# greenbox.net
KiCad netlist of a schematic drawn in EAGLE
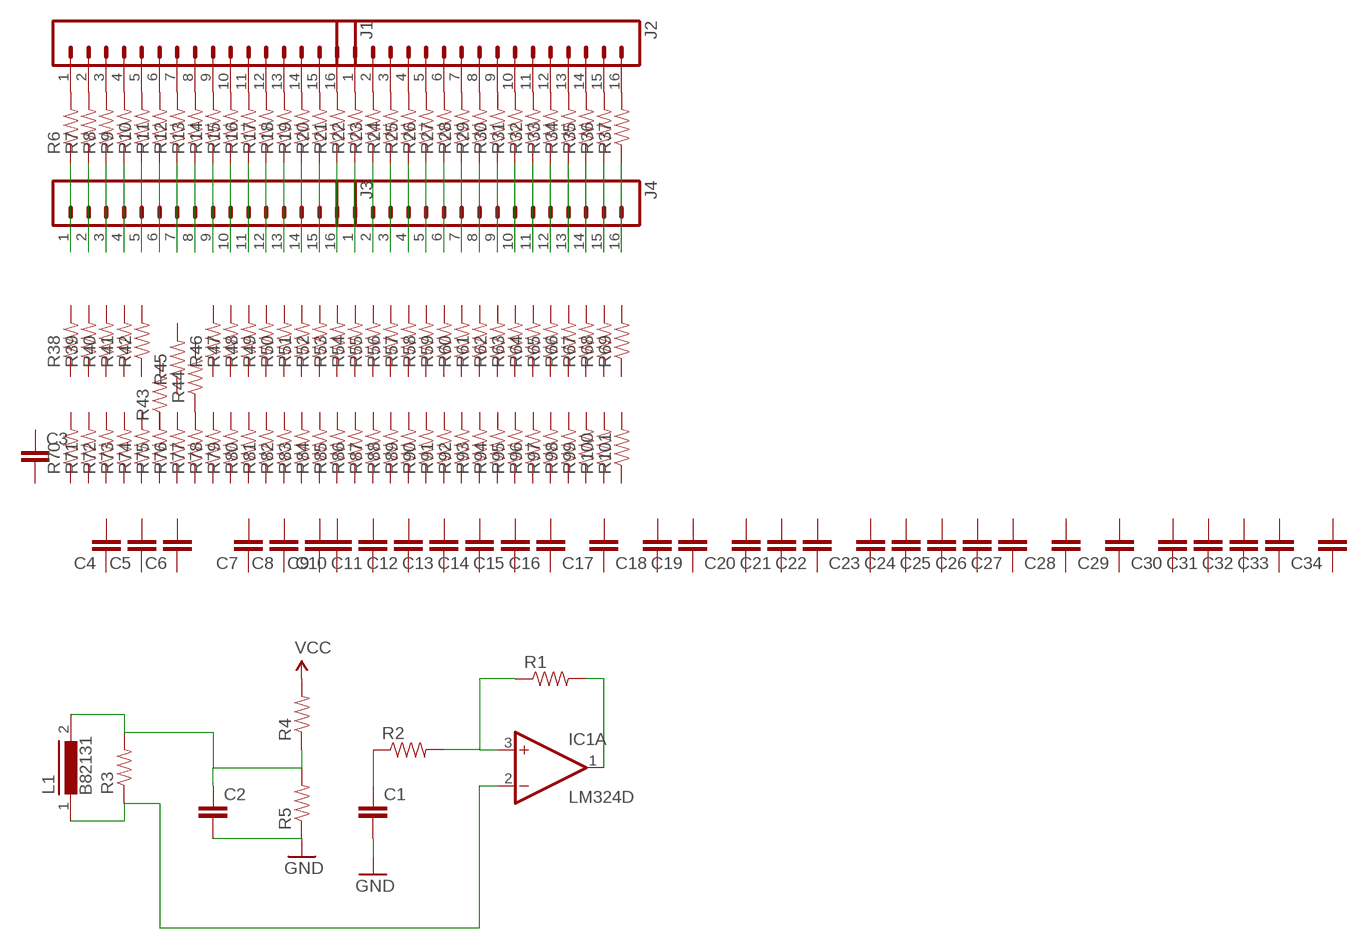
[diagram p0: schematic, sheet 1]

(export (version "E")
  (design (tool "Eeschema 10.0.6"))
  (components
    (comp (ref "C1")
      (value "CAP0603-CAP")
      (footprint "eagle-import:0603-CAP")
      (libsource (lib "eagle-import") (part "SparkFun-Passives_CAP0603-CAP"))
    )
    (comp (ref "C2")
      (value "CAP0603-CAP")
      (footprint "eagle-import:0603-CAP")
      (libsource (lib "eagle-import") (part "SparkFun-Passives_CAP0603-CAP"))
    )
    (comp (ref "C3")
      (value "CAP0603-CAP")
      (footprint "eagle-import:0603-CAP")
      (libsource (lib "eagle-import") (part "CAP0603-CAP"))
    )
    (comp (ref "C4")
      (value "CAP0603-CAP")
      (footprint "eagle-import:0603-CAP")
      (libsource (lib "eagle-import") (part "CAP0603-CAP"))
    )
    (comp (ref "C5")
      (value "CAP0603-CAP")
      (footprint "eagle-import:0603-CAP")
      (libsource (lib "eagle-import") (part "CAP0603-CAP"))
    )
    (comp (ref "C6")
      (value "CAP0603-CAP")
      (footprint "eagle-import:0603-CAP")
      (libsource (lib "eagle-import") (part "CAP0603-CAP"))
    )
    (comp (ref "C7")
      (value "CAP0603-CAP")
      (footprint "eagle-import:0603-CAP")
      (libsource (lib "eagle-import") (part "CAP0603-CAP"))
    )
    (comp (ref "C8")
      (value "CAP0603-CAP")
      (footprint "eagle-import:0603-CAP")
      (libsource (lib "eagle-import") (part "CAP0603-CAP"))
    )
    (comp (ref "C9")
      (value "CAP0603-CAP")
      (footprint "eagle-import:0603-CAP")
      (libsource (lib "eagle-import") (part "CAP0603-CAP"))
    )
    (comp (ref "C10")
      (value "CAP0603-CAP")
      (footprint "eagle-import:0603-CAP")
      (libsource (lib "eagle-import") (part "CAP0603-CAP"))
    )
    (comp (ref "C11")
      (value "CAP0603-CAP")
      (footprint "eagle-import:0603-CAP")
      (libsource (lib "eagle-import") (part "CAP0603-CAP"))
    )
    (comp (ref "C12")
      (value "CAP0603-CAP")
      (footprint "eagle-import:0603-CAP")
      (libsource (lib "eagle-import") (part "CAP0603-CAP"))
    )
    (comp (ref "C13")
      (value "CAP0603-CAP")
      (footprint "eagle-import:0603-CAP")
      (libsource (lib "eagle-import") (part "CAP0603-CAP"))
    )
    (comp (ref "C14")
      (value "CAP0603-CAP")
      (footprint "eagle-import:0603-CAP")
      (libsource (lib "eagle-import") (part "CAP0603-CAP"))
    )
    (comp (ref "C15")
      (value "CAP0603-CAP")
      (footprint "eagle-import:0603-CAP")
      (libsource (lib "eagle-import") (part "CAP0603-CAP"))
    )
    (comp (ref "C16")
      (value "CAP0603-CAP")
      (footprint "eagle-import:0603-CAP")
      (libsource (lib "eagle-import") (part "CAP0603-CAP"))
    )
    (comp (ref "C17")
      (value "CAP0603-CAP")
      (footprint "eagle-import:0603-CAP")
      (libsource (lib "eagle-import") (part "CAP0603-CAP"))
    )
    (comp (ref "C18")
      (value "CAP0603-CAP")
      (footprint "eagle-import:0603-CAP")
      (libsource (lib "eagle-import") (part "CAP0603-CAP"))
    )
    (comp (ref "C19")
      (value "CAP0603-CAP")
      (footprint "eagle-import:0603-CAP")
      (libsource (lib "eagle-import") (part "CAP0603-CAP"))
    )
    (comp (ref "C20")
      (value "CAP0603-CAP")
      (footprint "eagle-import:0603-CAP")
      (libsource (lib "eagle-import") (part "CAP0603-CAP"))
    )
    (comp (ref "C21")
      (value "CAP0603-CAP")
      (footprint "eagle-import:0603-CAP")
      (libsource (lib "eagle-import") (part "CAP0603-CAP"))
    )
    (comp (ref "C22")
      (value "CAP0603-CAP")
      (footprint "eagle-import:0603-CAP")
      (libsource (lib "eagle-import") (part "CAP0603-CAP"))
    )
    (comp (ref "C23")
      (value "CAP0603-CAP")
      (footprint "eagle-import:0603-CAP")
      (libsource (lib "eagle-import") (part "CAP0603-CAP"))
    )
    (comp (ref "C24")
      (value "CAP0603-CAP")
      (footprint "eagle-import:0603-CAP")
      (libsource (lib "eagle-import") (part "CAP0603-CAP"))
    )
    (comp (ref "C25")
      (value "CAP0603-CAP")
      (footprint "eagle-import:0603-CAP")
      (libsource (lib "eagle-import") (part "CAP0603-CAP"))
    )
    (comp (ref "C26")
      (value "CAP0603-CAP")
      (footprint "eagle-import:0603-CAP")
      (libsource (lib "eagle-import") (part "CAP0603-CAP"))
    )
    (comp (ref "C27")
      (value "CAP0603-CAP")
      (footprint "eagle-import:0603-CAP")
      (libsource (lib "eagle-import") (part "CAP0603-CAP"))
    )
    (comp (ref "C28")
      (value "CAP0603-CAP")
      (footprint "eagle-import:0603-CAP")
      (libsource (lib "eagle-import") (part "CAP0603-CAP"))
    )
    (comp (ref "C29")
      (value "CAP0603-CAP")
      (footprint "eagle-import:0603-CAP")
      (libsource (lib "eagle-import") (part "CAP0603-CAP"))
    )
    (comp (ref "C30")
      (value "CAP0603-CAP")
      (footprint "eagle-import:0603-CAP")
      (libsource (lib "eagle-import") (part "CAP0603-CAP"))
    )
    (comp (ref "C31")
      (value "CAP0603-CAP")
      (footprint "eagle-import:0603-CAP")
      (libsource (lib "eagle-import") (part "CAP0603-CAP"))
    )
    (comp (ref "C32")
      (value "CAP0603-CAP")
      (footprint "eagle-import:0603-CAP")
      (libsource (lib "eagle-import") (part "CAP0603-CAP"))
    )
    (comp (ref "C33")
      (value "CAP0603-CAP")
      (footprint "eagle-import:0603-CAP")
      (libsource (lib "eagle-import") (part "CAP0603-CAP"))
    )
    (comp (ref "C34")
      (value "CAP0603-CAP")
      (footprint "eagle-import:0603-CAP")
      (libsource (lib "eagle-import") (part "CAP0603-CAP"))
    )
    (comp (ref "IC1")
      (value "LM324D")
      (footprint "eagle-import:SO14")
      (libsource (lib "eagle-import") (part "LM324D"))
    )
    (comp (ref "J1")
      (value "M16LOCK")
      (footprint "eagle-import:1X16_LOCK")
      (libsource (lib "eagle-import") (part "M16LOCK"))
    )
    (comp (ref "J2")
      (value "M16LOCK")
      (footprint "eagle-import:1X16_LOCK")
      (libsource (lib "eagle-import") (part "M16LOCK"))
    )
    (comp (ref "J3")
      (value "M16LOCK")
      (footprint "eagle-import:1X16_LOCK")
      (libsource (lib "eagle-import") (part "M16LOCK"))
    )
    (comp (ref "J4")
      (value "M16LOCK")
      (footprint "eagle-import:1X16_LOCK")
      (libsource (lib "eagle-import") (part "M16LOCK"))
    )
    (comp (ref "L1")
      (value "B82131")
      (footprint "eagle-import:SUKW1-17")
      (libsource (lib "eagle-import") (part "B82131"))
    )
    (comp (ref "R1")
      (value "RESISTOR0603")
      (footprint "eagle-import:0603-RES")
      (libsource (lib "eagle-import") (part "RESISTOR0603"))
    )
    (comp (ref "R2")
      (value "RESISTOR0603")
      (footprint "eagle-import:0603-RES")
      (libsource (lib "eagle-import") (part "RESISTOR0603"))
    )
    (comp (ref "R3")
      (value "RESISTOR0603-RES")
      (footprint "eagle-import:0603-RES")
      (libsource (lib "eagle-import") (part "RESISTOR0603-RES"))
    )
    (comp (ref "R4")
      (value "RESISTOR0603-RES")
      (footprint "eagle-import:0603-RES")
      (libsource (lib "eagle-import") (part "RESISTOR0603-RES"))
    )
    (comp (ref "R5")
      (value "RESISTOR0603-RES")
      (footprint "eagle-import:0603-RES")
      (libsource (lib "eagle-import") (part "RESISTOR0603-RES"))
    )
    (comp (ref "R6")
      (value "RESISTOR0603-RES")
      (footprint "eagle-import:0603-RES")
      (libsource (lib "eagle-import") (part "RESISTOR0603-RES"))
    )
    (comp (ref "R7")
      (value "RESISTOR0603-RES")
      (footprint "eagle-import:0603-RES")
      (libsource (lib "eagle-import") (part "RESISTOR0603-RES"))
    )
    (comp (ref "R8")
      (value "RESISTOR0603-RES")
      (footprint "eagle-import:0603-RES")
      (libsource (lib "eagle-import") (part "RESISTOR0603-RES"))
    )
    (comp (ref "R9")
      (value "RESISTOR0603-RES")
      (footprint "eagle-import:0603-RES")
      (libsource (lib "eagle-import") (part "RESISTOR0603-RES"))
    )
    (comp (ref "R10")
      (value "RESISTOR0603-RES")
      (footprint "eagle-import:0603-RES")
      (libsource (lib "eagle-import") (part "RESISTOR0603-RES"))
    )
    (comp (ref "R11")
      (value "RESISTOR0603-RES")
      (footprint "eagle-import:0603-RES")
      (libsource (lib "eagle-import") (part "RESISTOR0603-RES"))
    )
    (comp (ref "R12")
      (value "RESISTOR0603-RES")
      (footprint "eagle-import:0603-RES")
      (libsource (lib "eagle-import") (part "RESISTOR0603-RES"))
    )
    (comp (ref "R13")
      (value "RESISTOR0603-RES")
      (footprint "eagle-import:0603-RES")
      (libsource (lib "eagle-import") (part "RESISTOR0603-RES"))
    )
    (comp (ref "R14")
      (value "RESISTOR0603-RES")
      (footprint "eagle-import:0603-RES")
      (libsource (lib "eagle-import") (part "RESISTOR0603-RES"))
    )
    (comp (ref "R15")
      (value "RESISTOR0603-RES")
      (footprint "eagle-import:0603-RES")
      (libsource (lib "eagle-import") (part "RESISTOR0603-RES"))
    )
    (comp (ref "R16")
      (value "RESISTOR0603-RES")
      (footprint "eagle-import:0603-RES")
      (libsource (lib "eagle-import") (part "RESISTOR0603-RES"))
    )
    (comp (ref "R17")
      (value "RESISTOR0603-RES")
      (footprint "eagle-import:0603-RES")
      (libsource (lib "eagle-import") (part "RESISTOR0603-RES"))
    )
    (comp (ref "R18")
      (value "RESISTOR0603-RES")
      (footprint "eagle-import:0603-RES")
      (libsource (lib "eagle-import") (part "RESISTOR0603-RES"))
    )
    (comp (ref "R19")
      (value "RESISTOR0603-RES")
      (footprint "eagle-import:0603-RES")
      (libsource (lib "eagle-import") (part "RESISTOR0603-RES"))
    )
    (comp (ref "R20")
      (value "RESISTOR0603-RES")
      (footprint "eagle-import:0603-RES")
      (libsource (lib "eagle-import") (part "RESISTOR0603-RES"))
    )
    (comp (ref "R21")
      (value "RESISTOR0603-RES")
      (footprint "eagle-import:0603-RES")
      (libsource (lib "eagle-import") (part "RESISTOR0603-RES"))
    )
    (comp (ref "R22")
      (value "RESISTOR0603-RES")
      (footprint "eagle-import:0603-RES")
      (libsource (lib "eagle-import") (part "RESISTOR0603-RES"))
    )
    (comp (ref "R23")
      (value "RESISTOR0603-RES")
      (footprint "eagle-import:0603-RES")
      (libsource (lib "eagle-import") (part "RESISTOR0603-RES"))
    )
    (comp (ref "R24")
      (value "RESISTOR0603-RES")
      (footprint "eagle-import:0603-RES")
      (libsource (lib "eagle-import") (part "RESISTOR0603-RES"))
    )
    (comp (ref "R25")
      (value "RESISTOR0603-RES")
      (footprint "eagle-import:0603-RES")
      (libsource (lib "eagle-import") (part "RESISTOR0603-RES"))
    )
    (comp (ref "R26")
      (value "RESISTOR0603-RES")
      (footprint "eagle-import:0603-RES")
      (libsource (lib "eagle-import") (part "RESISTOR0603-RES"))
    )
    (comp (ref "R27")
      (value "RESISTOR0603-RES")
      (footprint "eagle-import:0603-RES")
      (libsource (lib "eagle-import") (part "RESISTOR0603-RES"))
    )
    (comp (ref "R28")
      (value "RESISTOR0603-RES")
      (footprint "eagle-import:0603-RES")
      (libsource (lib "eagle-import") (part "RESISTOR0603-RES"))
    )
    (comp (ref "R29")
      (value "RESISTOR0603-RES")
      (footprint "eagle-import:0603-RES")
      (libsource (lib "eagle-import") (part "RESISTOR0603-RES"))
    )
    (comp (ref "R30")
      (value "RESISTOR0603-RES")
      (footprint "eagle-import:0603-RES")
      (libsource (lib "eagle-import") (part "RESISTOR0603-RES"))
    )
    (comp (ref "R31")
      (value "RESISTOR0603-RES")
      (footprint "eagle-import:0603-RES")
      (libsource (lib "eagle-import") (part "RESISTOR0603-RES"))
    )
    (comp (ref "R32")
      (value "RESISTOR0603-RES")
      (footprint "eagle-import:0603-RES")
      (libsource (lib "eagle-import") (part "RESISTOR0603-RES"))
    )
    (comp (ref "R33")
      (value "RESISTOR0603-RES")
      (footprint "eagle-import:0603-RES")
      (libsource (lib "eagle-import") (part "RESISTOR0603-RES"))
    )
    (comp (ref "R34")
      (value "RESISTOR0603-RES")
      (footprint "eagle-import:0603-RES")
      (libsource (lib "eagle-import") (part "RESISTOR0603-RES"))
    )
    (comp (ref "R35")
      (value "RESISTOR0603-RES")
      (footprint "eagle-import:0603-RES")
      (libsource (lib "eagle-import") (part "RESISTOR0603-RES"))
    )
    (comp (ref "R36")
      (value "RESISTOR0603-RES")
      (footprint "eagle-import:0603-RES")
      (libsource (lib "eagle-import") (part "RESISTOR0603-RES"))
    )
    (comp (ref "R37")
      (value "RESISTOR0603-RES")
      (footprint "eagle-import:0603-RES")
      (libsource (lib "eagle-import") (part "RESISTOR0603-RES"))
    )
    (comp (ref "R38")
      (value "RESISTOR0603-RES")
      (footprint "eagle-import:0603-RES")
      (libsource (lib "eagle-import") (part "RESISTOR0603-RES"))
    )
    (comp (ref "R39")
      (value "RESISTOR0603-RES")
      (footprint "eagle-import:0603-RES")
      (libsource (lib "eagle-import") (part "RESISTOR0603-RES"))
    )
    (comp (ref "R40")
      (value "RESISTOR0603-RES")
      (footprint "eagle-import:0603-RES")
      (libsource (lib "eagle-import") (part "RESISTOR0603-RES"))
    )
    (comp (ref "R41")
      (value "RESISTOR0603-RES")
      (footprint "eagle-import:0603-RES")
      (libsource (lib "eagle-import") (part "RESISTOR0603-RES"))
    )
    (comp (ref "R42")
      (value "RESISTOR0603-RES")
      (footprint "eagle-import:0603-RES")
      (libsource (lib "eagle-import") (part "RESISTOR0603-RES"))
    )
    (comp (ref "R43")
      (value "RESISTOR0603-RES")
      (footprint "eagle-import:0603-RES")
      (libsource (lib "eagle-import") (part "RESISTOR0603-RES"))
    )
    (comp (ref "R44")
      (value "RESISTOR0603-RES")
      (footprint "eagle-import:0603-RES")
      (libsource (lib "eagle-import") (part "RESISTOR0603-RES"))
    )
    (comp (ref "R45")
      (value "RESISTOR0603-RES")
      (footprint "eagle-import:0603-RES")
      (libsource (lib "eagle-import") (part "RESISTOR0603-RES"))
    )
    (comp (ref "R46")
      (value "RESISTOR0603-RES")
      (footprint "eagle-import:0603-RES")
      (libsource (lib "eagle-import") (part "RESISTOR0603-RES"))
    )
    (comp (ref "R47")
      (value "RESISTOR0603-RES")
      (footprint "eagle-import:0603-RES")
      (libsource (lib "eagle-import") (part "RESISTOR0603-RES"))
    )
    (comp (ref "R48")
      (value "RESISTOR0603-RES")
      (footprint "eagle-import:0603-RES")
      (libsource (lib "eagle-import") (part "RESISTOR0603-RES"))
    )
    (comp (ref "R49")
      (value "RESISTOR0603-RES")
      (footprint "eagle-import:0603-RES")
      (libsource (lib "eagle-import") (part "RESISTOR0603-RES"))
    )
    (comp (ref "R50")
      (value "RESISTOR0603-RES")
      (footprint "eagle-import:0603-RES")
      (libsource (lib "eagle-import") (part "RESISTOR0603-RES"))
    )
    (comp (ref "R51")
      (value "RESISTOR0603-RES")
      (footprint "eagle-import:0603-RES")
      (libsource (lib "eagle-import") (part "RESISTOR0603-RES"))
    )
    (comp (ref "R52")
      (value "RESISTOR0603-RES")
      (footprint "eagle-import:0603-RES")
      (libsource (lib "eagle-import") (part "RESISTOR0603-RES"))
    )
    (comp (ref "R53")
      (value "RESISTOR0603-RES")
      (footprint "eagle-import:0603-RES")
      (libsource (lib "eagle-import") (part "RESISTOR0603-RES"))
    )
    (comp (ref "R54")
      (value "RESISTOR0603-RES")
      (footprint "eagle-import:0603-RES")
      (libsource (lib "eagle-import") (part "RESISTOR0603-RES"))
    )
    (comp (ref "R55")
      (value "RESISTOR0603-RES")
      (footprint "eagle-import:0603-RES")
      (libsource (lib "eagle-import") (part "RESISTOR0603-RES"))
    )
    (comp (ref "R56")
      (value "RESISTOR0603-RES")
      (footprint "eagle-import:0603-RES")
      (libsource (lib "eagle-import") (part "RESISTOR0603-RES"))
    )
    (comp (ref "R57")
      (value "RESISTOR0603-RES")
      (footprint "eagle-import:0603-RES")
      (libsource (lib "eagle-import") (part "RESISTOR0603-RES"))
    )
    (comp (ref "R58")
      (value "RESISTOR0603-RES")
      (footprint "eagle-import:0603-RES")
      (libsource (lib "eagle-import") (part "RESISTOR0603-RES"))
    )
    (comp (ref "R59")
      (value "RESISTOR0603-RES")
      (footprint "eagle-import:0603-RES")
      (libsource (lib "eagle-import") (part "RESISTOR0603-RES"))
    )
    (comp (ref "R60")
      (value "RESISTOR0603-RES")
      (footprint "eagle-import:0603-RES")
      (libsource (lib "eagle-import") (part "RESISTOR0603-RES"))
    )
    (comp (ref "R61")
      (value "RESISTOR0603-RES")
      (footprint "eagle-import:0603-RES")
      (libsource (lib "eagle-import") (part "RESISTOR0603-RES"))
    )
    (comp (ref "R62")
      (value "RESISTOR0603-RES")
      (footprint "eagle-import:0603-RES")
      (libsource (lib "eagle-import") (part "RESISTOR0603-RES"))
    )
    (comp (ref "R63")
      (value "RESISTOR0603-RES")
      (footprint "eagle-import:0603-RES")
      (libsource (lib "eagle-import") (part "RESISTOR0603-RES"))
    )
    (comp (ref "R64")
      (value "RESISTOR0603-RES")
      (footprint "eagle-import:0603-RES")
      (libsource (lib "eagle-import") (part "RESISTOR0603-RES"))
    )
    (comp (ref "R65")
      (value "RESISTOR0603-RES")
      (footprint "eagle-import:0603-RES")
      (libsource (lib "eagle-import") (part "RESISTOR0603-RES"))
    )
    (comp (ref "R66")
      (value "RESISTOR0603-RES")
      (footprint "eagle-import:0603-RES")
      (libsource (lib "eagle-import") (part "RESISTOR0603-RES"))
    )
    (comp (ref "R67")
      (value "RESISTOR0603-RES")
      (footprint "eagle-import:0603-RES")
      (libsource (lib "eagle-import") (part "RESISTOR0603-RES"))
    )
    (comp (ref "R68")
      (value "RESISTOR0603-RES")
      (footprint "eagle-import:0603-RES")
      (libsource (lib "eagle-import") (part "RESISTOR0603-RES"))
    )
    (comp (ref "R69")
      (value "RESISTOR0603-RES")
      (footprint "eagle-import:0603-RES")
      (libsource (lib "eagle-import") (part "RESISTOR0603-RES"))
    )
    (comp (ref "R70")
      (value "RESISTOR0603-RES")
      (footprint "eagle-import:0603-RES")
      (libsource (lib "eagle-import") (part "RESISTOR0603-RES"))
    )
    (comp (ref "R71")
      (value "RESISTOR0603-RES")
      (footprint "eagle-import:0603-RES")
      (libsource (lib "eagle-import") (part "RESISTOR0603-RES"))
    )
    (comp (ref "R72")
      (value "RESISTOR0603-RES")
      (footprint "eagle-import:0603-RES")
      (libsource (lib "eagle-import") (part "RESISTOR0603-RES"))
    )
    (comp (ref "R73")
      (value "RESISTOR0603-RES")
      (footprint "eagle-import:0603-RES")
      (libsource (lib "eagle-import") (part "RESISTOR0603-RES"))
    )
    (comp (ref "R74")
      (value "RESISTOR0603-RES")
      (footprint "eagle-import:0603-RES")
      (libsource (lib "eagle-import") (part "RESISTOR0603-RES"))
    )
    (comp (ref "R75")
      (value "RESISTOR0603-RES")
      (footprint "eagle-import:0603-RES")
      (libsource (lib "eagle-import") (part "RESISTOR0603-RES"))
    )
    (comp (ref "R76")
      (value "RESISTOR0603-RES")
      (footprint "eagle-import:0603-RES")
      (libsource (lib "eagle-import") (part "RESISTOR0603-RES"))
    )
    (comp (ref "R77")
      (value "RESISTOR0603-RES")
      (footprint "eagle-import:0603-RES")
      (libsource (lib "eagle-import") (part "RESISTOR0603-RES"))
    )
    (comp (ref "R78")
      (value "RESISTOR0603-RES")
      (footprint "eagle-import:0603-RES")
      (libsource (lib "eagle-import") (part "RESISTOR0603-RES"))
    )
    (comp (ref "R79")
      (value "RESISTOR0603-RES")
      (footprint "eagle-import:0603-RES")
      (libsource (lib "eagle-import") (part "RESISTOR0603-RES"))
    )
    (comp (ref "R80")
      (value "RESISTOR0603-RES")
      (footprint "eagle-import:0603-RES")
      (libsource (lib "eagle-import") (part "RESISTOR0603-RES"))
    )
    (comp (ref "R81")
      (value "RESISTOR0603-RES")
      (footprint "eagle-import:0603-RES")
      (libsource (lib "eagle-import") (part "RESISTOR0603-RES"))
    )
    (comp (ref "R82")
      (value "RESISTOR0603-RES")
      (footprint "eagle-import:0603-RES")
      (libsource (lib "eagle-import") (part "RESISTOR0603-RES"))
    )
    (comp (ref "R83")
      (value "RESISTOR0603-RES")
      (footprint "eagle-import:0603-RES")
      (libsource (lib "eagle-import") (part "RESISTOR0603-RES"))
    )
    (comp (ref "R84")
      (value "RESISTOR0603-RES")
      (footprint "eagle-import:0603-RES")
      (libsource (lib "eagle-import") (part "RESISTOR0603-RES"))
    )
    (comp (ref "R85")
      (value "RESISTOR0603-RES")
      (footprint "eagle-import:0603-RES")
      (libsource (lib "eagle-import") (part "RESISTOR0603-RES"))
    )
    (comp (ref "R86")
      (value "RESISTOR0603-RES")
      (footprint "eagle-import:0603-RES")
      (libsource (lib "eagle-import") (part "RESISTOR0603-RES"))
    )
    (comp (ref "R87")
      (value "RESISTOR0603-RES")
      (footprint "eagle-import:0603-RES")
      (libsource (lib "eagle-import") (part "RESISTOR0603-RES"))
    )
    (comp (ref "R88")
      (value "RESISTOR0603-RES")
      (footprint "eagle-import:0603-RES")
      (libsource (lib "eagle-import") (part "RESISTOR0603-RES"))
    )
    (comp (ref "R89")
      (value "RESISTOR0603-RES")
      (footprint "eagle-import:0603-RES")
      (libsource (lib "eagle-import") (part "RESISTOR0603-RES"))
    )
    (comp (ref "R90")
      (value "RESISTOR0603-RES")
      (footprint "eagle-import:0603-RES")
      (libsource (lib "eagle-import") (part "RESISTOR0603-RES"))
    )
    (comp (ref "R91")
      (value "RESISTOR0603-RES")
      (footprint "eagle-import:0603-RES")
      (libsource (lib "eagle-import") (part "RESISTOR0603-RES"))
    )
    (comp (ref "R92")
      (value "RESISTOR0603-RES")
      (footprint "eagle-import:0603-RES")
      (libsource (lib "eagle-import") (part "RESISTOR0603-RES"))
    )
    (comp (ref "R93")
      (value "RESISTOR0603-RES")
      (footprint "eagle-import:0603-RES")
      (libsource (lib "eagle-import") (part "RESISTOR0603-RES"))
    )
    (comp (ref "R94")
      (value "RESISTOR0603-RES")
      (footprint "eagle-import:0603-RES")
      (libsource (lib "eagle-import") (part "RESISTOR0603-RES"))
    )
    (comp (ref "R95")
      (value "RESISTOR0603-RES")
      (footprint "eagle-import:0603-RES")
      (libsource (lib "eagle-import") (part "RESISTOR0603-RES"))
    )
    (comp (ref "R96")
      (value "RESISTOR0603-RES")
      (footprint "eagle-import:0603-RES")
      (libsource (lib "eagle-import") (part "RESISTOR0603-RES"))
    )
    (comp (ref "R97")
      (value "RESISTOR0603-RES")
      (footprint "eagle-import:0603-RES")
      (libsource (lib "eagle-import") (part "RESISTOR0603-RES"))
    )
    (comp (ref "R98")
      (value "RESISTOR0603-RES")
      (footprint "eagle-import:0603-RES")
      (libsource (lib "eagle-import") (part "RESISTOR0603-RES"))
    )
    (comp (ref "R99")
      (value "RESISTOR0603-RES")
      (footprint "eagle-import:0603-RES")
      (libsource (lib "eagle-import") (part "RESISTOR0603-RES"))
    )
    (comp (ref "R100")
      (value "RESISTOR0603-RES")
      (footprint "eagle-import:0603-RES")
      (libsource (lib "eagle-import") (part "RESISTOR0603-RES"))
    )
    (comp (ref "R101")
      (value "RESISTOR0603-RES")
      (footprint "eagle-import:0603-RES")
      (libsource (lib "eagle-import") (part "RESISTOR0603-RES"))
    )
  )
  (nets
    (net (code "1") (name "GND") (class "Default")
      (node (ref "C1") (pin "2") (pinfunction "2_2") (pintype "passive"))
      (node (ref "C2") (pin "2") (pinfunction "2_2") (pintype "passive"))
      (node (ref "R5") (pin "1") (pinfunction "1_1") (pintype "passive"))
    )
    (net (code "2") (name "Net-(C1-Pad1)") (class "Default")
      (node (ref "C1") (pin "1") (pinfunction "1_1") (pintype "passive"))
      (node (ref "R2") (pin "1") (pinfunction "1_1") (pintype "passive"))
    )
    (net (code "3") (name "Net-(C2-Pad1)") (class "Default")
      (node (ref "C2") (pin "1") (pinfunction "1_1") (pintype "passive"))
      (node (ref "L1") (pin "2") (pinfunction "2_2") (pintype "passive"))
      (node (ref "R3") (pin "2") (pinfunction "2_2") (pintype "passive"))
      (node (ref "R4") (pin "1") (pinfunction "1_1") (pintype "passive"))
      (node (ref "R5") (pin "2") (pinfunction "2_2") (pintype "passive"))
    )
    (net (code "4") (name "Net-(IC1A-+IN)") (class "Default")
      (node (ref "IC1") (pin "3") (pinfunction "+IN_3") (pintype "input"))
      (node (ref "R1") (pin "1") (pinfunction "1_1") (pintype "passive"))
      (node (ref "R2") (pin "2") (pinfunction "2_2") (pintype "passive"))
    )
    (net (code "5") (name "Net-(IC1A--IN)") (class "Default")
      (node (ref "IC1") (pin "2") (pinfunction "-IN_2") (pintype "input"))
      (node (ref "L1") (pin "1") (pinfunction "1_1") (pintype "passive"))
      (node (ref "R3") (pin "1") (pinfunction "1_1") (pintype "passive"))
    )
    (net (code "6") (name "Net-(IC1A-OUT)") (class "Default")
      (node (ref "IC1") (pin "1") (pinfunction "OUT_1") (pintype "output"))
      (node (ref "R1") (pin "2") (pinfunction "2_2") (pintype "passive"))
    )
    (net (code "7") (name "Net-(J1-Pad1)") (class "Default")
      (node (ref "J1") (pin "1") (pinfunction "1_1") (pintype "passive"))
      (node (ref "R6") (pin "2") (pinfunction "2_2") (pintype "passive"))
    )
    (net (code "8") (name "Net-(J1-Pad2)") (class "Default")
      (node (ref "J1") (pin "2") (pinfunction "2_2") (pintype "passive"))
      (node (ref "R7") (pin "2") (pinfunction "2_2") (pintype "passive"))
    )
    (net (code "9") (name "Net-(J1-Pad3)") (class "Default")
      (node (ref "J1") (pin "3") (pinfunction "3_3") (pintype "passive"))
      (node (ref "R8") (pin "2") (pinfunction "2_2") (pintype "passive"))
    )
    (net (code "10") (name "Net-(J1-Pad4)") (class "Default")
      (node (ref "J1") (pin "4") (pinfunction "4_4") (pintype "passive"))
      (node (ref "R9") (pin "2") (pinfunction "2_2") (pintype "passive"))
    )
    (net (code "11") (name "Net-(J1-Pad5)") (class "Default")
      (node (ref "J1") (pin "5") (pinfunction "5_5") (pintype "passive"))
      (node (ref "R10") (pin "2") (pinfunction "2_2") (pintype "passive"))
    )
    (net (code "12") (name "Net-(J1-Pad6)") (class "Default")
      (node (ref "J1") (pin "6") (pinfunction "6_6") (pintype "passive"))
      (node (ref "R11") (pin "2") (pinfunction "2_2") (pintype "passive"))
    )
    (net (code "13") (name "Net-(J1-Pad7)") (class "Default")
      (node (ref "J1") (pin "7") (pinfunction "7_7") (pintype "passive"))
      (node (ref "R12") (pin "2") (pinfunction "2_2") (pintype "passive"))
    )
    (net (code "14") (name "Net-(J1-Pad8)") (class "Default")
      (node (ref "J1") (pin "8") (pinfunction "8_8") (pintype "passive"))
      (node (ref "R13") (pin "2") (pinfunction "2_2") (pintype "passive"))
    )
    (net (code "15") (name "Net-(J1-Pad9)") (class "Default")
      (node (ref "J1") (pin "9") (pinfunction "9_9") (pintype "passive"))
      (node (ref "R14") (pin "2") (pinfunction "2_2") (pintype "passive"))
    )
    (net (code "16") (name "Net-(J1-Pad10)") (class "Default")
      (node (ref "J1") (pin "10") (pinfunction "10_10") (pintype "passive"))
      (node (ref "R15") (pin "2") (pinfunction "2_2") (pintype "passive"))
    )
    (net (code "17") (name "Net-(J1-Pad11)") (class "Default")
      (node (ref "J1") (pin "11") (pinfunction "11_11") (pintype "passive"))
      (node (ref "R16") (pin "2") (pinfunction "2_2") (pintype "passive"))
    )
    (net (code "18") (name "Net-(J1-Pad12)") (class "Default")
      (node (ref "J1") (pin "12") (pinfunction "12_12") (pintype "passive"))
      (node (ref "R17") (pin "2") (pinfunction "2_2") (pintype "passive"))
    )
    (net (code "19") (name "Net-(J1-Pad13)") (class "Default")
      (node (ref "J1") (pin "13") (pinfunction "13_13") (pintype "passive"))
      (node (ref "R18") (pin "2") (pinfunction "2_2") (pintype "passive"))
    )
    (net (code "20") (name "Net-(J1-Pad14)") (class "Default")
      (node (ref "J1") (pin "14") (pinfunction "14_14") (pintype "passive"))
      (node (ref "R19") (pin "2") (pinfunction "2_2") (pintype "passive"))
    )
    (net (code "21") (name "Net-(J1-Pad15)") (class "Default")
      (node (ref "J1") (pin "15") (pinfunction "15_15") (pintype "passive"))
      (node (ref "R20") (pin "2") (pinfunction "2_2") (pintype "passive"))
    )
    (net (code "22") (name "Net-(J1-Pad16)") (class "Default")
      (node (ref "J1") (pin "16") (pinfunction "16_16") (pintype "passive"))
      (node (ref "R21") (pin "2") (pinfunction "2_2") (pintype "passive"))
    )
    (net (code "23") (name "Net-(J2-Pad1)") (class "Default")
      (node (ref "J2") (pin "1") (pinfunction "1_1") (pintype "passive"))
      (node (ref "R22") (pin "2") (pinfunction "2_2") (pintype "passive"))
    )
    (net (code "24") (name "Net-(J2-Pad2)") (class "Default")
      (node (ref "J2") (pin "2") (pinfunction "2_2") (pintype "passive"))
      (node (ref "R23") (pin "2") (pinfunction "2_2") (pintype "passive"))
    )
    (net (code "25") (name "Net-(J2-Pad3)") (class "Default")
      (node (ref "J2") (pin "3") (pinfunction "3_3") (pintype "passive"))
      (node (ref "R24") (pin "2") (pinfunction "2_2") (pintype "passive"))
    )
    (net (code "26") (name "Net-(J2-Pad4)") (class "Default")
      (node (ref "J2") (pin "4") (pinfunction "4_4") (pintype "passive"))
      (node (ref "R25") (pin "2") (pinfunction "2_2") (pintype "passive"))
    )
    (net (code "27") (name "Net-(J2-Pad5)") (class "Default")
      (node (ref "J2") (pin "5") (pinfunction "5_5") (pintype "passive"))
      (node (ref "R26") (pin "2") (pinfunction "2_2") (pintype "passive"))
    )
    (net (code "28") (name "Net-(J2-Pad6)") (class "Default")
      (node (ref "J2") (pin "6") (pinfunction "6_6") (pintype "passive"))
      (node (ref "R27") (pin "2") (pinfunction "2_2") (pintype "passive"))
    )
    (net (code "29") (name "Net-(J2-Pad7)") (class "Default")
      (node (ref "J2") (pin "7") (pinfunction "7_7") (pintype "passive"))
      (node (ref "R28") (pin "2") (pinfunction "2_2") (pintype "passive"))
    )
    (net (code "30") (name "Net-(J2-Pad8)") (class "Default")
      (node (ref "J2") (pin "8") (pinfunction "8_8") (pintype "passive"))
      (node (ref "R29") (pin "2") (pinfunction "2_2") (pintype "passive"))
    )
    (net (code "31") (name "Net-(J2-Pad9)") (class "Default")
      (node (ref "J2") (pin "9") (pinfunction "9_9") (pintype "passive"))
      (node (ref "R30") (pin "2") (pinfunction "2_2") (pintype "passive"))
    )
    (net (code "32") (name "Net-(J2-Pad10)") (class "Default")
      (node (ref "J2") (pin "10") (pinfunction "10_10") (pintype "passive"))
      (node (ref "R31") (pin "2") (pinfunction "2_2") (pintype "passive"))
    )
    (net (code "33") (name "Net-(J2-Pad11)") (class "Default")
      (node (ref "J2") (pin "11") (pinfunction "11_11") (pintype "passive"))
      (node (ref "R32") (pin "2") (pinfunction "2_2") (pintype "passive"))
    )
    (net (code "34") (name "Net-(J2-Pad12)") (class "Default")
      (node (ref "J2") (pin "12") (pinfunction "12_12") (pintype "passive"))
      (node (ref "R33") (pin "2") (pinfunction "2_2") (pintype "passive"))
    )
    (net (code "35") (name "Net-(J2-Pad13)") (class "Default")
      (node (ref "J2") (pin "13") (pinfunction "13_13") (pintype "passive"))
      (node (ref "R34") (pin "2") (pinfunction "2_2") (pintype "passive"))
    )
    (net (code "36") (name "Net-(J2-Pad14)") (class "Default")
      (node (ref "J2") (pin "14") (pinfunction "14_14") (pintype "passive"))
      (node (ref "R35") (pin "2") (pinfunction "2_2") (pintype "passive"))
    )
    (net (code "37") (name "Net-(J2-Pad15)") (class "Default")
      (node (ref "J2") (pin "15") (pinfunction "15_15") (pintype "passive"))
      (node (ref "R36") (pin "2") (pinfunction "2_2") (pintype "passive"))
    )
    (net (code "38") (name "Net-(J2-Pad16)") (class "Default")
      (node (ref "J2") (pin "16") (pinfunction "16_16") (pintype "passive"))
      (node (ref "R37") (pin "2") (pinfunction "2_2") (pintype "passive"))
    )
    (net (code "39") (name "Net-(J3-Pad1)") (class "Default")
      (node (ref "J3") (pin "1") (pinfunction "1_1") (pintype "passive"))
      (node (ref "R6") (pin "1") (pinfunction "1_1") (pintype "passive"))
    )
    (net (code "40") (name "Net-(J3-Pad2)") (class "Default")
      (node (ref "J3") (pin "2") (pinfunction "2_2") (pintype "passive"))
      (node (ref "R7") (pin "1") (pinfunction "1_1") (pintype "passive"))
    )
    (net (code "41") (name "Net-(J3-Pad3)") (class "Default")
      (node (ref "J3") (pin "3") (pinfunction "3_3") (pintype "passive"))
      (node (ref "R8") (pin "1") (pinfunction "1_1") (pintype "passive"))
    )
    (net (code "42") (name "Net-(J3-Pad4)") (class "Default")
      (node (ref "J3") (pin "4") (pinfunction "4_4") (pintype "passive"))
      (node (ref "R9") (pin "1") (pinfunction "1_1") (pintype "passive"))
    )
    (net (code "43") (name "Net-(J3-Pad5)") (class "Default")
      (node (ref "J3") (pin "5") (pinfunction "5_5") (pintype "passive"))
      (node (ref "R10") (pin "1") (pinfunction "1_1") (pintype "passive"))
    )
    (net (code "44") (name "Net-(J3-Pad6)") (class "Default")
      (node (ref "J3") (pin "6") (pinfunction "6_6") (pintype "passive"))
      (node (ref "R11") (pin "1") (pinfunction "1_1") (pintype "passive"))
    )
    (net (code "45") (name "Net-(J3-Pad7)") (class "Default")
      (node (ref "J3") (pin "7") (pinfunction "7_7") (pintype "passive"))
      (node (ref "R12") (pin "1") (pinfunction "1_1") (pintype "passive"))
    )
    (net (code "46") (name "Net-(J3-Pad8)") (class "Default")
      (node (ref "J3") (pin "8") (pinfunction "8_8") (pintype "passive"))
      (node (ref "R13") (pin "1") (pinfunction "1_1") (pintype "passive"))
    )
    (net (code "47") (name "Net-(J3-Pad9)") (class "Default")
      (node (ref "J3") (pin "9") (pinfunction "9_9") (pintype "passive"))
      (node (ref "R14") (pin "1") (pinfunction "1_1") (pintype "passive"))
    )
    (net (code "48") (name "Net-(J3-Pad10)") (class "Default")
      (node (ref "J3") (pin "10") (pinfunction "10_10") (pintype "passive"))
      (node (ref "R15") (pin "1") (pinfunction "1_1") (pintype "passive"))
    )
    (net (code "49") (name "Net-(J3-Pad11)") (class "Default")
      (node (ref "J3") (pin "11") (pinfunction "11_11") (pintype "passive"))
      (node (ref "R16") (pin "1") (pinfunction "1_1") (pintype "passive"))
    )
    (net (code "50") (name "Net-(J3-Pad12)") (class "Default")
      (node (ref "J3") (pin "12") (pinfunction "12_12") (pintype "passive"))
      (node (ref "R17") (pin "1") (pinfunction "1_1") (pintype "passive"))
    )
    (net (code "51") (name "Net-(J3-Pad13)") (class "Default")
      (node (ref "J3") (pin "13") (pinfunction "13_13") (pintype "passive"))
      (node (ref "R18") (pin "1") (pinfunction "1_1") (pintype "passive"))
    )
    (net (code "52") (name "Net-(J3-Pad14)") (class "Default")
      (node (ref "J3") (pin "14") (pinfunction "14_14") (pintype "passive"))
      (node (ref "R19") (pin "1") (pinfunction "1_1") (pintype "passive"))
    )
    (net (code "53") (name "Net-(J3-Pad15)") (class "Default")
      (node (ref "J3") (pin "15") (pinfunction "15_15") (pintype "passive"))
      (node (ref "R20") (pin "1") (pinfunction "1_1") (pintype "passive"))
    )
    (net (code "54") (name "Net-(J3-Pad16)") (class "Default")
      (node (ref "J3") (pin "16") (pinfunction "16_16") (pintype "passive"))
      (node (ref "R21") (pin "1") (pinfunction "1_1") (pintype "passive"))
    )
    (net (code "55") (name "Net-(J4-Pad1)") (class "Default")
      (node (ref "J4") (pin "1") (pinfunction "1_1") (pintype "passive"))
      (node (ref "R22") (pin "1") (pinfunction "1_1") (pintype "passive"))
    )
    (net (code "56") (name "Net-(J4-Pad2)") (class "Default")
      (node (ref "J4") (pin "2") (pinfunction "2_2") (pintype "passive"))
      (node (ref "R23") (pin "1") (pinfunction "1_1") (pintype "passive"))
    )
    (net (code "57") (name "Net-(J4-Pad3)") (class "Default")
      (node (ref "J4") (pin "3") (pinfunction "3_3") (pintype "passive"))
      (node (ref "R24") (pin "1") (pinfunction "1_1") (pintype "passive"))
    )
    (net (code "58") (name "Net-(J4-Pad4)") (class "Default")
      (node (ref "J4") (pin "4") (pinfunction "4_4") (pintype "passive"))
      (node (ref "R25") (pin "1") (pinfunction "1_1") (pintype "passive"))
    )
    (net (code "59") (name "Net-(J4-Pad5)") (class "Default")
      (node (ref "J4") (pin "5") (pinfunction "5_5") (pintype "passive"))
      (node (ref "R26") (pin "1") (pinfunction "1_1") (pintype "passive"))
    )
    (net (code "60") (name "Net-(J4-Pad6)") (class "Default")
      (node (ref "J4") (pin "6") (pinfunction "6_6") (pintype "passive"))
      (node (ref "R27") (pin "1") (pinfunction "1_1") (pintype "passive"))
    )
    (net (code "61") (name "Net-(J4-Pad7)") (class "Default")
      (node (ref "J4") (pin "7") (pinfunction "7_7") (pintype "passive"))
      (node (ref "R28") (pin "1") (pinfunction "1_1") (pintype "passive"))
    )
    (net (code "62") (name "Net-(J4-Pad8)") (class "Default")
      (node (ref "J4") (pin "8") (pinfunction "8_8") (pintype "passive"))
      (node (ref "R29") (pin "1") (pinfunction "1_1") (pintype "passive"))
    )
    (net (code "63") (name "Net-(J4-Pad9)") (class "Default")
      (node (ref "J4") (pin "9") (pinfunction "9_9") (pintype "passive"))
      (node (ref "R30") (pin "1") (pinfunction "1_1") (pintype "passive"))
    )
    (net (code "64") (name "Net-(J4-Pad10)") (class "Default")
      (node (ref "J4") (pin "10") (pinfunction "10_10") (pintype "passive"))
      (node (ref "R31") (pin "1") (pinfunction "1_1") (pintype "passive"))
    )
    (net (code "65") (name "Net-(J4-Pad11)") (class "Default")
      (node (ref "J4") (pin "11") (pinfunction "11_11") (pintype "passive"))
      (node (ref "R32") (pin "1") (pinfunction "1_1") (pintype "passive"))
    )
    (net (code "66") (name "Net-(J4-Pad12)") (class "Default")
      (node (ref "J4") (pin "12") (pinfunction "12_12") (pintype "passive"))
      (node (ref "R33") (pin "1") (pinfunction "1_1") (pintype "passive"))
    )
    (net (code "67") (name "Net-(J4-Pad13)") (class "Default")
      (node (ref "J4") (pin "13") (pinfunction "13_13") (pintype "passive"))
      (node (ref "R34") (pin "1") (pinfunction "1_1") (pintype "passive"))
    )
    (net (code "68") (name "Net-(J4-Pad14)") (class "Default")
      (node (ref "J4") (pin "14") (pinfunction "14_14") (pintype "passive"))
      (node (ref "R35") (pin "1") (pinfunction "1_1") (pintype "passive"))
    )
    (net (code "69") (name "Net-(J4-Pad15)") (class "Default")
      (node (ref "J4") (pin "15") (pinfunction "15_15") (pintype "passive"))
      (node (ref "R36") (pin "1") (pinfunction "1_1") (pintype "passive"))
    )
    (net (code "70") (name "Net-(J4-Pad16)") (class "Default")
      (node (ref "J4") (pin "16") (pinfunction "16_16") (pintype "passive"))
      (node (ref "R37") (pin "1") (pinfunction "1_1") (pintype "passive"))
    )
    (net (code "71") (name "Net-(R44-Pad1)") (class "Default")
      (node (ref "R44") (pin "1") (pinfunction "1_1") (pintype "passive"))
      (node (ref "R77") (pin "2") (pinfunction "2_2") (pintype "passive"))
    )
    (net (code "72") (name "VCC") (class "Default")
      (node (ref "R4") (pin "2") (pinfunction "2_2") (pintype "passive"))
    )
    (net (code "73") (name "unconnected-(C3-Pad1)") (class "Default")
      (node (ref "C3") (pin "1") (pinfunction "1_1") (pintype "passive"))
    )
    (net (code "74") (name "unconnected-(C3-Pad2)") (class "Default")
      (node (ref "C3") (pin "2") (pinfunction "2_2") (pintype "passive"))
    )
    (net (code "75") (name "unconnected-(C4-Pad1)") (class "Default")
      (node (ref "C4") (pin "1") (pinfunction "1_1") (pintype "passive"))
    )
    (net (code "76") (name "unconnected-(C4-Pad2)") (class "Default")
      (node (ref "C4") (pin "2") (pinfunction "2_2") (pintype "passive"))
    )
    (net (code "77") (name "unconnected-(C5-Pad1)") (class "Default")
      (node (ref "C5") (pin "1") (pinfunction "1_1") (pintype "passive"))
    )
    (net (code "78") (name "unconnected-(C5-Pad2)") (class "Default")
      (node (ref "C5") (pin "2") (pinfunction "2_2") (pintype "passive"))
    )
    (net (code "79") (name "unconnected-(C6-Pad1)") (class "Default")
      (node (ref "C6") (pin "1") (pinfunction "1_1") (pintype "passive"))
    )
    (net (code "80") (name "unconnected-(C6-Pad2)") (class "Default")
      (node (ref "C6") (pin "2") (pinfunction "2_2") (pintype "passive"))
    )
    (net (code "81") (name "unconnected-(C7-Pad1)") (class "Default")
      (node (ref "C7") (pin "1") (pinfunction "1_1") (pintype "passive"))
    )
    (net (code "82") (name "unconnected-(C7-Pad2)") (class "Default")
      (node (ref "C7") (pin "2") (pinfunction "2_2") (pintype "passive"))
    )
    (net (code "83") (name "unconnected-(C8-Pad1)") (class "Default")
      (node (ref "C8") (pin "1") (pinfunction "1_1") (pintype "passive"))
    )
    (net (code "84") (name "unconnected-(C8-Pad2)") (class "Default")
      (node (ref "C8") (pin "2") (pinfunction "2_2") (pintype "passive"))
    )
    (net (code "85") (name "unconnected-(C9-Pad1)") (class "Default")
      (node (ref "C9") (pin "1") (pinfunction "1_1") (pintype "passive"))
    )
    (net (code "86") (name "unconnected-(C9-Pad2)") (class "Default")
      (node (ref "C9") (pin "2") (pinfunction "2_2") (pintype "passive"))
    )
    (net (code "87") (name "unconnected-(C10-Pad1)") (class "Default")
      (node (ref "C10") (pin "1") (pinfunction "1_1") (pintype "passive"))
    )
    (net (code "88") (name "unconnected-(C10-Pad2)") (class "Default")
      (node (ref "C10") (pin "2") (pinfunction "2_2") (pintype "passive"))
    )
    (net (code "89") (name "unconnected-(C11-Pad1)") (class "Default")
      (node (ref "C11") (pin "1") (pinfunction "1_1") (pintype "passive"))
    )
    (net (code "90") (name "unconnected-(C11-Pad2)") (class "Default")
      (node (ref "C11") (pin "2") (pinfunction "2_2") (pintype "passive"))
    )
    (net (code "91") (name "unconnected-(C12-Pad1)") (class "Default")
      (node (ref "C12") (pin "1") (pinfunction "1_1") (pintype "passive"))
    )
    (net (code "92") (name "unconnected-(C12-Pad2)") (class "Default")
      (node (ref "C12") (pin "2") (pinfunction "2_2") (pintype "passive"))
    )
    (net (code "93") (name "unconnected-(C13-Pad1)") (class "Default")
      (node (ref "C13") (pin "1") (pinfunction "1_1") (pintype "passive"))
    )
    (net (code "94") (name "unconnected-(C13-Pad2)") (class "Default")
      (node (ref "C13") (pin "2") (pinfunction "2_2") (pintype "passive"))
    )
    (net (code "95") (name "unconnected-(C14-Pad1)") (class "Default")
      (node (ref "C14") (pin "1") (pinfunction "1_1") (pintype "passive"))
    )
    (net (code "96") (name "unconnected-(C14-Pad2)") (class "Default")
      (node (ref "C14") (pin "2") (pinfunction "2_2") (pintype "passive"))
    )
    (net (code "97") (name "unconnected-(C15-Pad1)") (class "Default")
      (node (ref "C15") (pin "1") (pinfunction "1_1") (pintype "passive"))
    )
    (net (code "98") (name "unconnected-(C15-Pad2)") (class "Default")
      (node (ref "C15") (pin "2") (pinfunction "2_2") (pintype "passive"))
    )
    (net (code "99") (name "unconnected-(C16-Pad1)") (class "Default")
      (node (ref "C16") (pin "1") (pinfunction "1_1") (pintype "passive"))
    )
    (net (code "100") (name "unconnected-(C16-Pad2)") (class "Default")
      (node (ref "C16") (pin "2") (pinfunction "2_2") (pintype "passive"))
    )
    (net (code "101") (name "unconnected-(C17-Pad1)") (class "Default")
      (node (ref "C17") (pin "1") (pinfunction "1_1") (pintype "passive"))
    )
    (net (code "102") (name "unconnected-(C17-Pad2)") (class "Default")
      (node (ref "C17") (pin "2") (pinfunction "2_2") (pintype "passive"))
    )
    (net (code "103") (name "unconnected-(C18-Pad1)") (class "Default")
      (node (ref "C18") (pin "1") (pinfunction "1_1") (pintype "passive"))
    )
    (net (code "104") (name "unconnected-(C18-Pad2)") (class "Default")
      (node (ref "C18") (pin "2") (pinfunction "2_2") (pintype "passive"))
    )
    (net (code "105") (name "unconnected-(C19-Pad1)") (class "Default")
      (node (ref "C19") (pin "1") (pinfunction "1_1") (pintype "passive"))
    )
    (net (code "106") (name "unconnected-(C19-Pad2)") (class "Default")
      (node (ref "C19") (pin "2") (pinfunction "2_2") (pintype "passive"))
    )
    (net (code "107") (name "unconnected-(C20-Pad1)") (class "Default")
      (node (ref "C20") (pin "1") (pinfunction "1_1") (pintype "passive"))
    )
    (net (code "108") (name "unconnected-(C20-Pad2)") (class "Default")
      (node (ref "C20") (pin "2") (pinfunction "2_2") (pintype "passive"))
    )
    (net (code "109") (name "unconnected-(C21-Pad1)") (class "Default")
      (node (ref "C21") (pin "1") (pinfunction "1_1") (pintype "passive"))
    )
    (net (code "110") (name "unconnected-(C21-Pad2)") (class "Default")
      (node (ref "C21") (pin "2") (pinfunction "2_2") (pintype "passive"))
    )
    (net (code "111") (name "unconnected-(C22-Pad1)") (class "Default")
      (node (ref "C22") (pin "1") (pinfunction "1_1") (pintype "passive"))
    )
    (net (code "112") (name "unconnected-(C22-Pad2)") (class "Default")
      (node (ref "C22") (pin "2") (pinfunction "2_2") (pintype "passive"))
    )
    (net (code "113") (name "unconnected-(C23-Pad1)") (class "Default")
      (node (ref "C23") (pin "1") (pinfunction "1_1") (pintype "passive"))
    )
    (net (code "114") (name "unconnected-(C23-Pad2)") (class "Default")
      (node (ref "C23") (pin "2") (pinfunction "2_2") (pintype "passive"))
    )
    (net (code "115") (name "unconnected-(C24-Pad1)") (class "Default")
      (node (ref "C24") (pin "1") (pinfunction "1_1") (pintype "passive"))
    )
    (net (code "116") (name "unconnected-(C24-Pad2)") (class "Default")
      (node (ref "C24") (pin "2") (pinfunction "2_2") (pintype "passive"))
    )
    (net (code "117") (name "unconnected-(C25-Pad1)") (class "Default")
      (node (ref "C25") (pin "1") (pinfunction "1_1") (pintype "passive"))
    )
    (net (code "118") (name "unconnected-(C25-Pad2)") (class "Default")
      (node (ref "C25") (pin "2") (pinfunction "2_2") (pintype "passive"))
    )
    (net (code "119") (name "unconnected-(C26-Pad1)") (class "Default")
      (node (ref "C26") (pin "1") (pinfunction "1_1") (pintype "passive"))
    )
    (net (code "120") (name "unconnected-(C26-Pad2)") (class "Default")
      (node (ref "C26") (pin "2") (pinfunction "2_2") (pintype "passive"))
    )
    (net (code "121") (name "unconnected-(C27-Pad1)") (class "Default")
      (node (ref "C27") (pin "1") (pinfunction "1_1") (pintype "passive"))
    )
    (net (code "122") (name "unconnected-(C27-Pad2)") (class "Default")
      (node (ref "C27") (pin "2") (pinfunction "2_2") (pintype "passive"))
    )
    (net (code "123") (name "unconnected-(C28-Pad1)") (class "Default")
      (node (ref "C28") (pin "1") (pinfunction "1_1") (pintype "passive"))
    )
    (net (code "124") (name "unconnected-(C28-Pad2)") (class "Default")
      (node (ref "C28") (pin "2") (pinfunction "2_2") (pintype "passive"))
    )
    (net (code "125") (name "unconnected-(C29-Pad1)") (class "Default")
      (node (ref "C29") (pin "1") (pinfunction "1_1") (pintype "passive"))
    )
    (net (code "126") (name "unconnected-(C29-Pad2)") (class "Default")
      (node (ref "C29") (pin "2") (pinfunction "2_2") (pintype "passive"))
    )
    (net (code "127") (name "unconnected-(C30-Pad1)") (class "Default")
      (node (ref "C30") (pin "1") (pinfunction "1_1") (pintype "passive"))
    )
    (net (code "128") (name "unconnected-(C30-Pad2)") (class "Default")
      (node (ref "C30") (pin "2") (pinfunction "2_2") (pintype "passive"))
    )
    (net (code "129") (name "unconnected-(C31-Pad1)") (class "Default")
      (node (ref "C31") (pin "1") (pinfunction "1_1") (pintype "passive"))
    )
    (net (code "130") (name "unconnected-(C31-Pad2)") (class "Default")
      (node (ref "C31") (pin "2") (pinfunction "2_2") (pintype "passive"))
    )
    (net (code "131") (name "unconnected-(C32-Pad1)") (class "Default")
      (node (ref "C32") (pin "1") (pinfunction "1_1") (pintype "passive"))
    )
    (net (code "132") (name "unconnected-(C32-Pad2)") (class "Default")
      (node (ref "C32") (pin "2") (pinfunction "2_2") (pintype "passive"))
    )
    (net (code "133") (name "unconnected-(C33-Pad1)") (class "Default")
      (node (ref "C33") (pin "1") (pinfunction "1_1") (pintype "passive"))
    )
    (net (code "134") (name "unconnected-(C33-Pad2)") (class "Default")
      (node (ref "C33") (pin "2") (pinfunction "2_2") (pintype "passive"))
    )
    (net (code "135") (name "unconnected-(C34-Pad1)") (class "Default")
      (node (ref "C34") (pin "1") (pinfunction "1_1") (pintype "passive"))
    )
    (net (code "136") (name "unconnected-(C34-Pad2)") (class "Default")
      (node (ref "C34") (pin "2") (pinfunction "2_2") (pintype "passive"))
    )
    (net (code "137") (name "unconnected-(R38-Pad1)") (class "Default")
      (node (ref "R38") (pin "1") (pinfunction "1_1") (pintype "passive"))
    )
    (net (code "138") (name "unconnected-(R38-Pad2)") (class "Default")
      (node (ref "R38") (pin "2") (pinfunction "2_2") (pintype "passive"))
    )
    (net (code "139") (name "unconnected-(R39-Pad1)") (class "Default")
      (node (ref "R39") (pin "1") (pinfunction "1_1") (pintype "passive"))
    )
    (net (code "140") (name "unconnected-(R39-Pad2)") (class "Default")
      (node (ref "R39") (pin "2") (pinfunction "2_2") (pintype "passive"))
    )
    (net (code "141") (name "unconnected-(R40-Pad1)") (class "Default")
      (node (ref "R40") (pin "1") (pinfunction "1_1") (pintype "passive"))
    )
    (net (code "142") (name "unconnected-(R40-Pad2)") (class "Default")
      (node (ref "R40") (pin "2") (pinfunction "2_2") (pintype "passive"))
    )
    (net (code "143") (name "unconnected-(R41-Pad1)") (class "Default")
      (node (ref "R41") (pin "1") (pinfunction "1_1") (pintype "passive"))
    )
    (net (code "144") (name "unconnected-(R41-Pad2)") (class "Default")
      (node (ref "R41") (pin "2") (pinfunction "2_2") (pintype "passive"))
    )
    (net (code "145") (name "unconnected-(R42-Pad1)") (class "Default")
      (node (ref "R42") (pin "1") (pinfunction "1_1") (pintype "passive"))
    )
    (net (code "146") (name "unconnected-(R42-Pad2)") (class "Default")
      (node (ref "R42") (pin "2") (pinfunction "2_2") (pintype "passive"))
    )
    (net (code "147") (name "unconnected-(R43-Pad1)") (class "Default")
      (node (ref "R43") (pin "1") (pinfunction "1_1") (pintype "passive"))
    )
    (net (code "148") (name "unconnected-(R43-Pad2)") (class "Default")
      (node (ref "R43") (pin "2") (pinfunction "2_2") (pintype "passive"))
    )
    (net (code "149") (name "unconnected-(R44-Pad2)") (class "Default")
      (node (ref "R44") (pin "2") (pinfunction "2_2") (pintype "passive"))
    )
    (net (code "150") (name "unconnected-(R45-Pad1)") (class "Default")
      (node (ref "R45") (pin "1") (pinfunction "1_1") (pintype "passive"))
    )
    (net (code "151") (name "unconnected-(R45-Pad2)") (class "Default")
      (node (ref "R45") (pin "2") (pinfunction "2_2") (pintype "passive"))
    )
    (net (code "152") (name "unconnected-(R46-Pad1)") (class "Default")
      (node (ref "R46") (pin "1") (pinfunction "1_1") (pintype "passive"))
    )
    (net (code "153") (name "unconnected-(R46-Pad2)") (class "Default")
      (node (ref "R46") (pin "2") (pinfunction "2_2") (pintype "passive"))
    )
    (net (code "154") (name "unconnected-(R47-Pad1)") (class "Default")
      (node (ref "R47") (pin "1") (pinfunction "1_1") (pintype "passive"))
    )
    (net (code "155") (name "unconnected-(R47-Pad2)") (class "Default")
      (node (ref "R47") (pin "2") (pinfunction "2_2") (pintype "passive"))
    )
    (net (code "156") (name "unconnected-(R48-Pad1)") (class "Default")
      (node (ref "R48") (pin "1") (pinfunction "1_1") (pintype "passive"))
    )
    (net (code "157") (name "unconnected-(R48-Pad2)") (class "Default")
      (node (ref "R48") (pin "2") (pinfunction "2_2") (pintype "passive"))
    )
    (net (code "158") (name "unconnected-(R49-Pad1)") (class "Default")
      (node (ref "R49") (pin "1") (pinfunction "1_1") (pintype "passive"))
    )
    (net (code "159") (name "unconnected-(R49-Pad2)") (class "Default")
      (node (ref "R49") (pin "2") (pinfunction "2_2") (pintype "passive"))
    )
    (net (code "160") (name "unconnected-(R50-Pad1)") (class "Default")
      (node (ref "R50") (pin "1") (pinfunction "1_1") (pintype "passive"))
    )
    (net (code "161") (name "unconnected-(R50-Pad2)") (class "Default")
      (node (ref "R50") (pin "2") (pinfunction "2_2") (pintype "passive"))
    )
    (net (code "162") (name "unconnected-(R51-Pad1)") (class "Default")
      (node (ref "R51") (pin "1") (pinfunction "1_1") (pintype "passive"))
    )
    (net (code "163") (name "unconnected-(R51-Pad2)") (class "Default")
      (node (ref "R51") (pin "2") (pinfunction "2_2") (pintype "passive"))
    )
    (net (code "164") (name "unconnected-(R52-Pad1)") (class "Default")
      (node (ref "R52") (pin "1") (pinfunction "1_1") (pintype "passive"))
    )
    (net (code "165") (name "unconnected-(R52-Pad2)") (class "Default")
      (node (ref "R52") (pin "2") (pinfunction "2_2") (pintype "passive"))
    )
    (net (code "166") (name "unconnected-(R53-Pad1)") (class "Default")
      (node (ref "R53") (pin "1") (pinfunction "1_1") (pintype "passive"))
    )
    (net (code "167") (name "unconnected-(R53-Pad2)") (class "Default")
      (node (ref "R53") (pin "2") (pinfunction "2_2") (pintype "passive"))
    )
    (net (code "168") (name "unconnected-(R54-Pad1)") (class "Default")
      (node (ref "R54") (pin "1") (pinfunction "1_1") (pintype "passive"))
    )
    (net (code "169") (name "unconnected-(R54-Pad2)") (class "Default")
      (node (ref "R54") (pin "2") (pinfunction "2_2") (pintype "passive"))
    )
    (net (code "170") (name "unconnected-(R55-Pad1)") (class "Default")
      (node (ref "R55") (pin "1") (pinfunction "1_1") (pintype "passive"))
    )
    (net (code "171") (name "unconnected-(R55-Pad2)") (class "Default")
      (node (ref "R55") (pin "2") (pinfunction "2_2") (pintype "passive"))
    )
    (net (code "172") (name "unconnected-(R56-Pad1)") (class "Default")
      (node (ref "R56") (pin "1") (pinfunction "1_1") (pintype "passive"))
    )
    (net (code "173") (name "unconnected-(R56-Pad2)") (class "Default")
      (node (ref "R56") (pin "2") (pinfunction "2_2") (pintype "passive"))
    )
    (net (code "174") (name "unconnected-(R57-Pad1)") (class "Default")
      (node (ref "R57") (pin "1") (pinfunction "1_1") (pintype "passive"))
    )
    (net (code "175") (name "unconnected-(R57-Pad2)") (class "Default")
      (node (ref "R57") (pin "2") (pinfunction "2_2") (pintype "passive"))
    )
    (net (code "176") (name "unconnected-(R58-Pad1)") (class "Default")
      (node (ref "R58") (pin "1") (pinfunction "1_1") (pintype "passive"))
    )
    (net (code "177") (name "unconnected-(R58-Pad2)") (class "Default")
      (node (ref "R58") (pin "2") (pinfunction "2_2") (pintype "passive"))
    )
    (net (code "178") (name "unconnected-(R59-Pad1)") (class "Default")
      (node (ref "R59") (pin "1") (pinfunction "1_1") (pintype "passive"))
    )
    (net (code "179") (name "unconnected-(R59-Pad2)") (class "Default")
      (node (ref "R59") (pin "2") (pinfunction "2_2") (pintype "passive"))
    )
    (net (code "180") (name "unconnected-(R60-Pad1)") (class "Default")
      (node (ref "R60") (pin "1") (pinfunction "1_1") (pintype "passive"))
    )
    (net (code "181") (name "unconnected-(R60-Pad2)") (class "Default")
      (node (ref "R60") (pin "2") (pinfunction "2_2") (pintype "passive"))
    )
    (net (code "182") (name "unconnected-(R61-Pad1)") (class "Default")
      (node (ref "R61") (pin "1") (pinfunction "1_1") (pintype "passive"))
    )
    (net (code "183") (name "unconnected-(R61-Pad2)") (class "Default")
      (node (ref "R61") (pin "2") (pinfunction "2_2") (pintype "passive"))
    )
    (net (code "184") (name "unconnected-(R62-Pad1)") (class "Default")
      (node (ref "R62") (pin "1") (pinfunction "1_1") (pintype "passive"))
    )
    (net (code "185") (name "unconnected-(R62-Pad2)") (class "Default")
      (node (ref "R62") (pin "2") (pinfunction "2_2") (pintype "passive"))
    )
    (net (code "186") (name "unconnected-(R63-Pad1)") (class "Default")
      (node (ref "R63") (pin "1") (pinfunction "1_1") (pintype "passive"))
    )
    (net (code "187") (name "unconnected-(R63-Pad2)") (class "Default")
      (node (ref "R63") (pin "2") (pinfunction "2_2") (pintype "passive"))
    )
    (net (code "188") (name "unconnected-(R64-Pad1)") (class "Default")
      (node (ref "R64") (pin "1") (pinfunction "1_1") (pintype "passive"))
    )
    (net (code "189") (name "unconnected-(R64-Pad2)") (class "Default")
      (node (ref "R64") (pin "2") (pinfunction "2_2") (pintype "passive"))
    )
    (net (code "190") (name "unconnected-(R65-Pad1)") (class "Default")
      (node (ref "R65") (pin "1") (pinfunction "1_1") (pintype "passive"))
    )
    (net (code "191") (name "unconnected-(R65-Pad2)") (class "Default")
      (node (ref "R65") (pin "2") (pinfunction "2_2") (pintype "passive"))
    )
    (net (code "192") (name "unconnected-(R66-Pad1)") (class "Default")
      (node (ref "R66") (pin "1") (pinfunction "1_1") (pintype "passive"))
    )
    (net (code "193") (name "unconnected-(R66-Pad2)") (class "Default")
      (node (ref "R66") (pin "2") (pinfunction "2_2") (pintype "passive"))
    )
    (net (code "194") (name "unconnected-(R67-Pad1)") (class "Default")
      (node (ref "R67") (pin "1") (pinfunction "1_1") (pintype "passive"))
    )
    (net (code "195") (name "unconnected-(R67-Pad2)") (class "Default")
      (node (ref "R67") (pin "2") (pinfunction "2_2") (pintype "passive"))
    )
    (net (code "196") (name "unconnected-(R68-Pad1)") (class "Default")
      (node (ref "R68") (pin "1") (pinfunction "1_1") (pintype "passive"))
    )
    (net (code "197") (name "unconnected-(R68-Pad2)") (class "Default")
      (node (ref "R68") (pin "2") (pinfunction "2_2") (pintype "passive"))
    )
    (net (code "198") (name "unconnected-(R69-Pad1)") (class "Default")
      (node (ref "R69") (pin "1") (pinfunction "1_1") (pintype "passive"))
    )
    (net (code "199") (name "unconnected-(R69-Pad2)") (class "Default")
      (node (ref "R69") (pin "2") (pinfunction "2_2") (pintype "passive"))
    )
    (net (code "200") (name "unconnected-(R70-Pad1)") (class "Default")
      (node (ref "R70") (pin "1") (pinfunction "1_1") (pintype "passive"))
    )
    (net (code "201") (name "unconnected-(R70-Pad2)") (class "Default")
      (node (ref "R70") (pin "2") (pinfunction "2_2") (pintype "passive"))
    )
    (net (code "202") (name "unconnected-(R71-Pad1)") (class "Default")
      (node (ref "R71") (pin "1") (pinfunction "1_1") (pintype "passive"))
    )
    (net (code "203") (name "unconnected-(R71-Pad2)") (class "Default")
      (node (ref "R71") (pin "2") (pinfunction "2_2") (pintype "passive"))
    )
    (net (code "204") (name "unconnected-(R72-Pad1)") (class "Default")
      (node (ref "R72") (pin "1") (pinfunction "1_1") (pintype "passive"))
    )
    (net (code "205") (name "unconnected-(R72-Pad2)") (class "Default")
      (node (ref "R72") (pin "2") (pinfunction "2_2") (pintype "passive"))
    )
    (net (code "206") (name "unconnected-(R73-Pad1)") (class "Default")
      (node (ref "R73") (pin "1") (pinfunction "1_1") (pintype "passive"))
    )
    (net (code "207") (name "unconnected-(R73-Pad2)") (class "Default")
      (node (ref "R73") (pin "2") (pinfunction "2_2") (pintype "passive"))
    )
    (net (code "208") (name "unconnected-(R74-Pad1)") (class "Default")
      (node (ref "R74") (pin "1") (pinfunction "1_1") (pintype "passive"))
    )
    (net (code "209") (name "unconnected-(R74-Pad2)") (class "Default")
      (node (ref "R74") (pin "2") (pinfunction "2_2") (pintype "passive"))
    )
    (net (code "210") (name "unconnected-(R75-Pad1)") (class "Default")
      (node (ref "R75") (pin "1") (pinfunction "1_1") (pintype "passive"))
    )
    (net (code "211") (name "unconnected-(R75-Pad2)") (class "Default")
      (node (ref "R75") (pin "2") (pinfunction "2_2") (pintype "passive"))
    )
    (net (code "212") (name "unconnected-(R76-Pad1)") (class "Default")
      (node (ref "R76") (pin "1") (pinfunction "1_1") (pintype "passive"))
    )
    (net (code "213") (name "unconnected-(R76-Pad2)") (class "Default")
      (node (ref "R76") (pin "2") (pinfunction "2_2") (pintype "passive"))
    )
    (net (code "214") (name "unconnected-(R77-Pad1)") (class "Default")
      (node (ref "R77") (pin "1") (pinfunction "1_1") (pintype "passive"))
    )
    (net (code "215") (name "unconnected-(R78-Pad1)") (class "Default")
      (node (ref "R78") (pin "1") (pinfunction "1_1") (pintype "passive"))
    )
    (net (code "216") (name "unconnected-(R78-Pad2)") (class "Default")
      (node (ref "R78") (pin "2") (pinfunction "2_2") (pintype "passive"))
    )
    (net (code "217") (name "unconnected-(R79-Pad1)") (class "Default")
      (node (ref "R79") (pin "1") (pinfunction "1_1") (pintype "passive"))
    )
    (net (code "218") (name "unconnected-(R79-Pad2)") (class "Default")
      (node (ref "R79") (pin "2") (pinfunction "2_2") (pintype "passive"))
    )
    (net (code "219") (name "unconnected-(R80-Pad1)") (class "Default")
      (node (ref "R80") (pin "1") (pinfunction "1_1") (pintype "passive"))
    )
    (net (code "220") (name "unconnected-(R80-Pad2)") (class "Default")
      (node (ref "R80") (pin "2") (pinfunction "2_2") (pintype "passive"))
    )
    (net (code "221") (name "unconnected-(R81-Pad1)") (class "Default")
      (node (ref "R81") (pin "1") (pinfunction "1_1") (pintype "passive"))
    )
    (net (code "222") (name "unconnected-(R81-Pad2)") (class "Default")
      (node (ref "R81") (pin "2") (pinfunction "2_2") (pintype "passive"))
    )
    (net (code "223") (name "unconnected-(R82-Pad1)") (class "Default")
      (node (ref "R82") (pin "1") (pinfunction "1_1") (pintype "passive"))
    )
    (net (code "224") (name "unconnected-(R82-Pad2)") (class "Default")
      (node (ref "R82") (pin "2") (pinfunction "2_2") (pintype "passive"))
    )
    (net (code "225") (name "unconnected-(R83-Pad1)") (class "Default")
      (node (ref "R83") (pin "1") (pinfunction "1_1") (pintype "passive"))
    )
    (net (code "226") (name "unconnected-(R83-Pad2)") (class "Default")
      (node (ref "R83") (pin "2") (pinfunction "2_2") (pintype "passive"))
    )
    (net (code "227") (name "unconnected-(R84-Pad1)") (class "Default")
      (node (ref "R84") (pin "1") (pinfunction "1_1") (pintype "passive"))
    )
    (net (code "228") (name "unconnected-(R84-Pad2)") (class "Default")
      (node (ref "R84") (pin "2") (pinfunction "2_2") (pintype "passive"))
    )
    (net (code "229") (name "unconnected-(R85-Pad1)") (class "Default")
      (node (ref "R85") (pin "1") (pinfunction "1_1") (pintype "passive"))
    )
    (net (code "230") (name "unconnected-(R85-Pad2)") (class "Default")
      (node (ref "R85") (pin "2") (pinfunction "2_2") (pintype "passive"))
    )
    (net (code "231") (name "unconnected-(R86-Pad1)") (class "Default")
      (node (ref "R86") (pin "1") (pinfunction "1_1") (pintype "passive"))
    )
    (net (code "232") (name "unconnected-(R86-Pad2)") (class "Default")
      (node (ref "R86") (pin "2") (pinfunction "2_2") (pintype "passive"))
    )
    (net (code "233") (name "unconnected-(R87-Pad1)") (class "Default")
      (node (ref "R87") (pin "1") (pinfunction "1_1") (pintype "passive"))
    )
    (net (code "234") (name "unconnected-(R87-Pad2)") (class "Default")
      (node (ref "R87") (pin "2") (pinfunction "2_2") (pintype "passive"))
    )
    (net (code "235") (name "unconnected-(R88-Pad1)") (class "Default")
      (node (ref "R88") (pin "1") (pinfunction "1_1") (pintype "passive"))
    )
    (net (code "236") (name "unconnected-(R88-Pad2)") (class "Default")
      (node (ref "R88") (pin "2") (pinfunction "2_2") (pintype "passive"))
    )
    (net (code "237") (name "unconnected-(R89-Pad1)") (class "Default")
      (node (ref "R89") (pin "1") (pinfunction "1_1") (pintype "passive"))
    )
    (net (code "238") (name "unconnected-(R89-Pad2)") (class "Default")
      (node (ref "R89") (pin "2") (pinfunction "2_2") (pintype "passive"))
    )
    (net (code "239") (name "unconnected-(R90-Pad1)") (class "Default")
      (node (ref "R90") (pin "1") (pinfunction "1_1") (pintype "passive"))
    )
    (net (code "240") (name "unconnected-(R90-Pad2)") (class "Default")
      (node (ref "R90") (pin "2") (pinfunction "2_2") (pintype "passive"))
    )
    (net (code "241") (name "unconnected-(R91-Pad1)") (class "Default")
      (node (ref "R91") (pin "1") (pinfunction "1_1") (pintype "passive"))
    )
    (net (code "242") (name "unconnected-(R91-Pad2)") (class "Default")
      (node (ref "R91") (pin "2") (pinfunction "2_2") (pintype "passive"))
    )
    (net (code "243") (name "unconnected-(R92-Pad1)") (class "Default")
      (node (ref "R92") (pin "1") (pinfunction "1_1") (pintype "passive"))
    )
    (net (code "244") (name "unconnected-(R92-Pad2)") (class "Default")
      (node (ref "R92") (pin "2") (pinfunction "2_2") (pintype "passive"))
    )
    (net (code "245") (name "unconnected-(R93-Pad1)") (class "Default")
      (node (ref "R93") (pin "1") (pinfunction "1_1") (pintype "passive"))
    )
    (net (code "246") (name "unconnected-(R93-Pad2)") (class "Default")
      (node (ref "R93") (pin "2") (pinfunction "2_2") (pintype "passive"))
    )
    (net (code "247") (name "unconnected-(R94-Pad1)") (class "Default")
      (node (ref "R94") (pin "1") (pinfunction "1_1") (pintype "passive"))
    )
    (net (code "248") (name "unconnected-(R94-Pad2)") (class "Default")
      (node (ref "R94") (pin "2") (pinfunction "2_2") (pintype "passive"))
    )
    (net (code "249") (name "unconnected-(R95-Pad1)") (class "Default")
      (node (ref "R95") (pin "1") (pinfunction "1_1") (pintype "passive"))
    )
    (net (code "250") (name "unconnected-(R95-Pad2)") (class "Default")
      (node (ref "R95") (pin "2") (pinfunction "2_2") (pintype "passive"))
    )
    (net (code "251") (name "unconnected-(R96-Pad1)") (class "Default")
      (node (ref "R96") (pin "1") (pinfunction "1_1") (pintype "passive"))
    )
    (net (code "252") (name "unconnected-(R96-Pad2)") (class "Default")
      (node (ref "R96") (pin "2") (pinfunction "2_2") (pintype "passive"))
    )
    (net (code "253") (name "unconnected-(R97-Pad1)") (class "Default")
      (node (ref "R97") (pin "1") (pinfunction "1_1") (pintype "passive"))
    )
    (net (code "254") (name "unconnected-(R97-Pad2)") (class "Default")
      (node (ref "R97") (pin "2") (pinfunction "2_2") (pintype "passive"))
    )
    (net (code "255") (name "unconnected-(R98-Pad1)") (class "Default")
      (node (ref "R98") (pin "1") (pinfunction "1_1") (pintype "passive"))
    )
    (net (code "256") (name "unconnected-(R98-Pad2)") (class "Default")
      (node (ref "R98") (pin "2") (pinfunction "2_2") (pintype "passive"))
    )
    (net (code "257") (name "unconnected-(R99-Pad1)") (class "Default")
      (node (ref "R99") (pin "1") (pinfunction "1_1") (pintype "passive"))
    )
    (net (code "258") (name "unconnected-(R99-Pad2)") (class "Default")
      (node (ref "R99") (pin "2") (pinfunction "2_2") (pintype "passive"))
    )
    (net (code "259") (name "unconnected-(R100-Pad1)") (class "Default")
      (node (ref "R100") (pin "1") (pinfunction "1_1") (pintype "passive"))
    )
    (net (code "260") (name "unconnected-(R100-Pad2)") (class "Default")
      (node (ref "R100") (pin "2") (pinfunction "2_2") (pintype "passive"))
    )
    (net (code "261") (name "unconnected-(R101-Pad1)") (class "Default")
      (node (ref "R101") (pin "1") (pinfunction "1_1") (pintype "passive"))
    )
    (net (code "262") (name "unconnected-(R101-Pad2)") (class "Default")
      (node (ref "R101") (pin "2") (pinfunction "2_2") (pintype "passive"))
    )
  )
)
